# arduino-shield.net
KiCad netlist of a schematic drawn in EAGLE
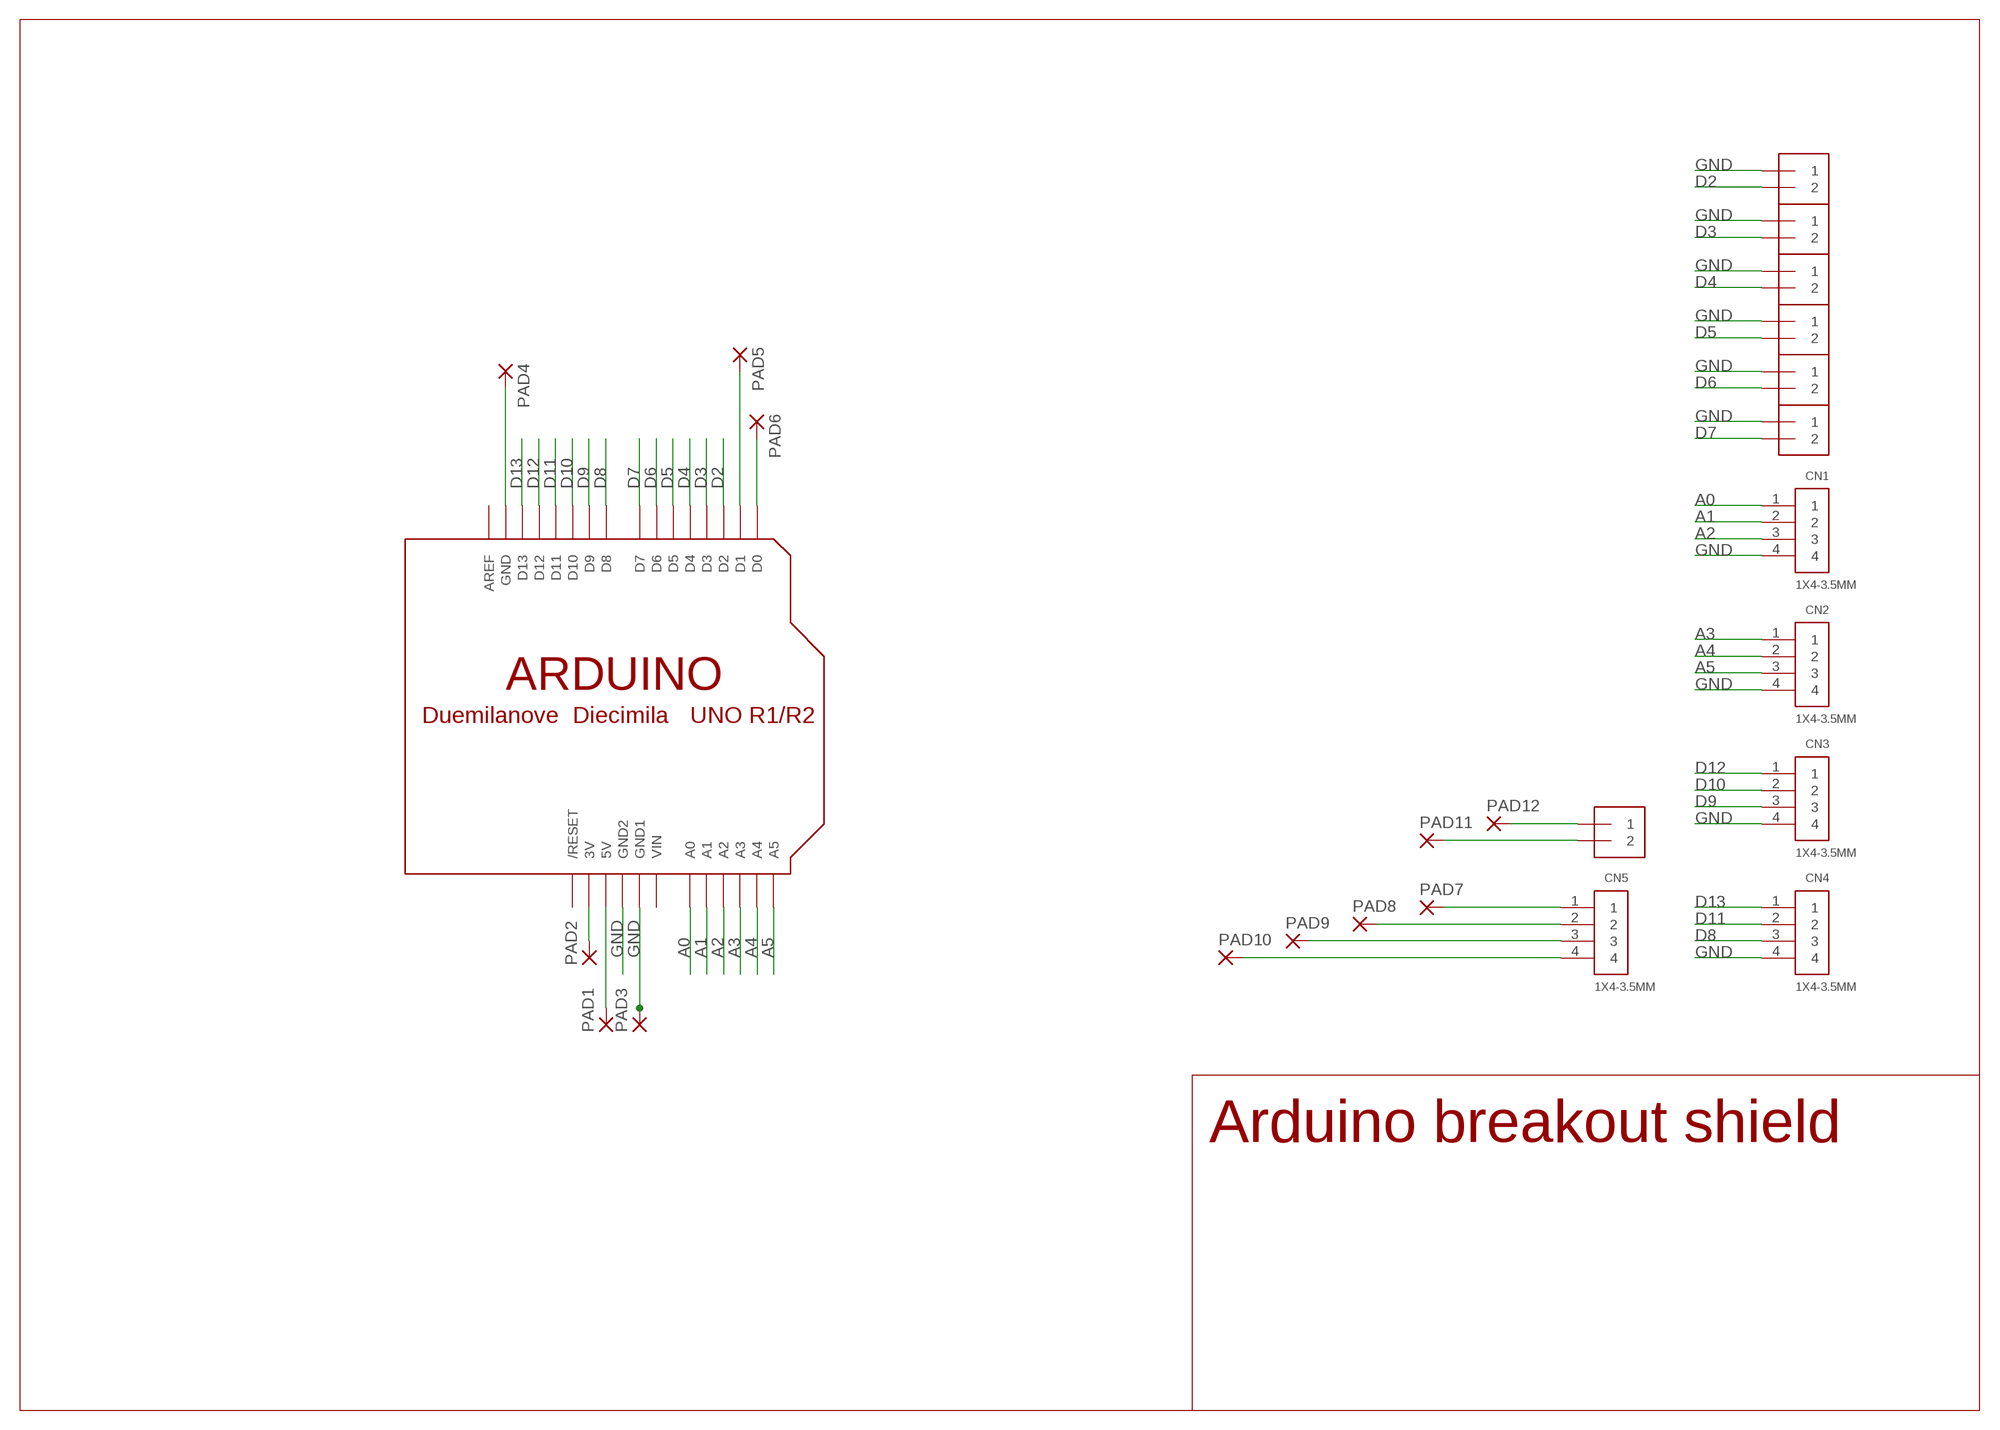
[diagram p0: schematic, sheet 1]
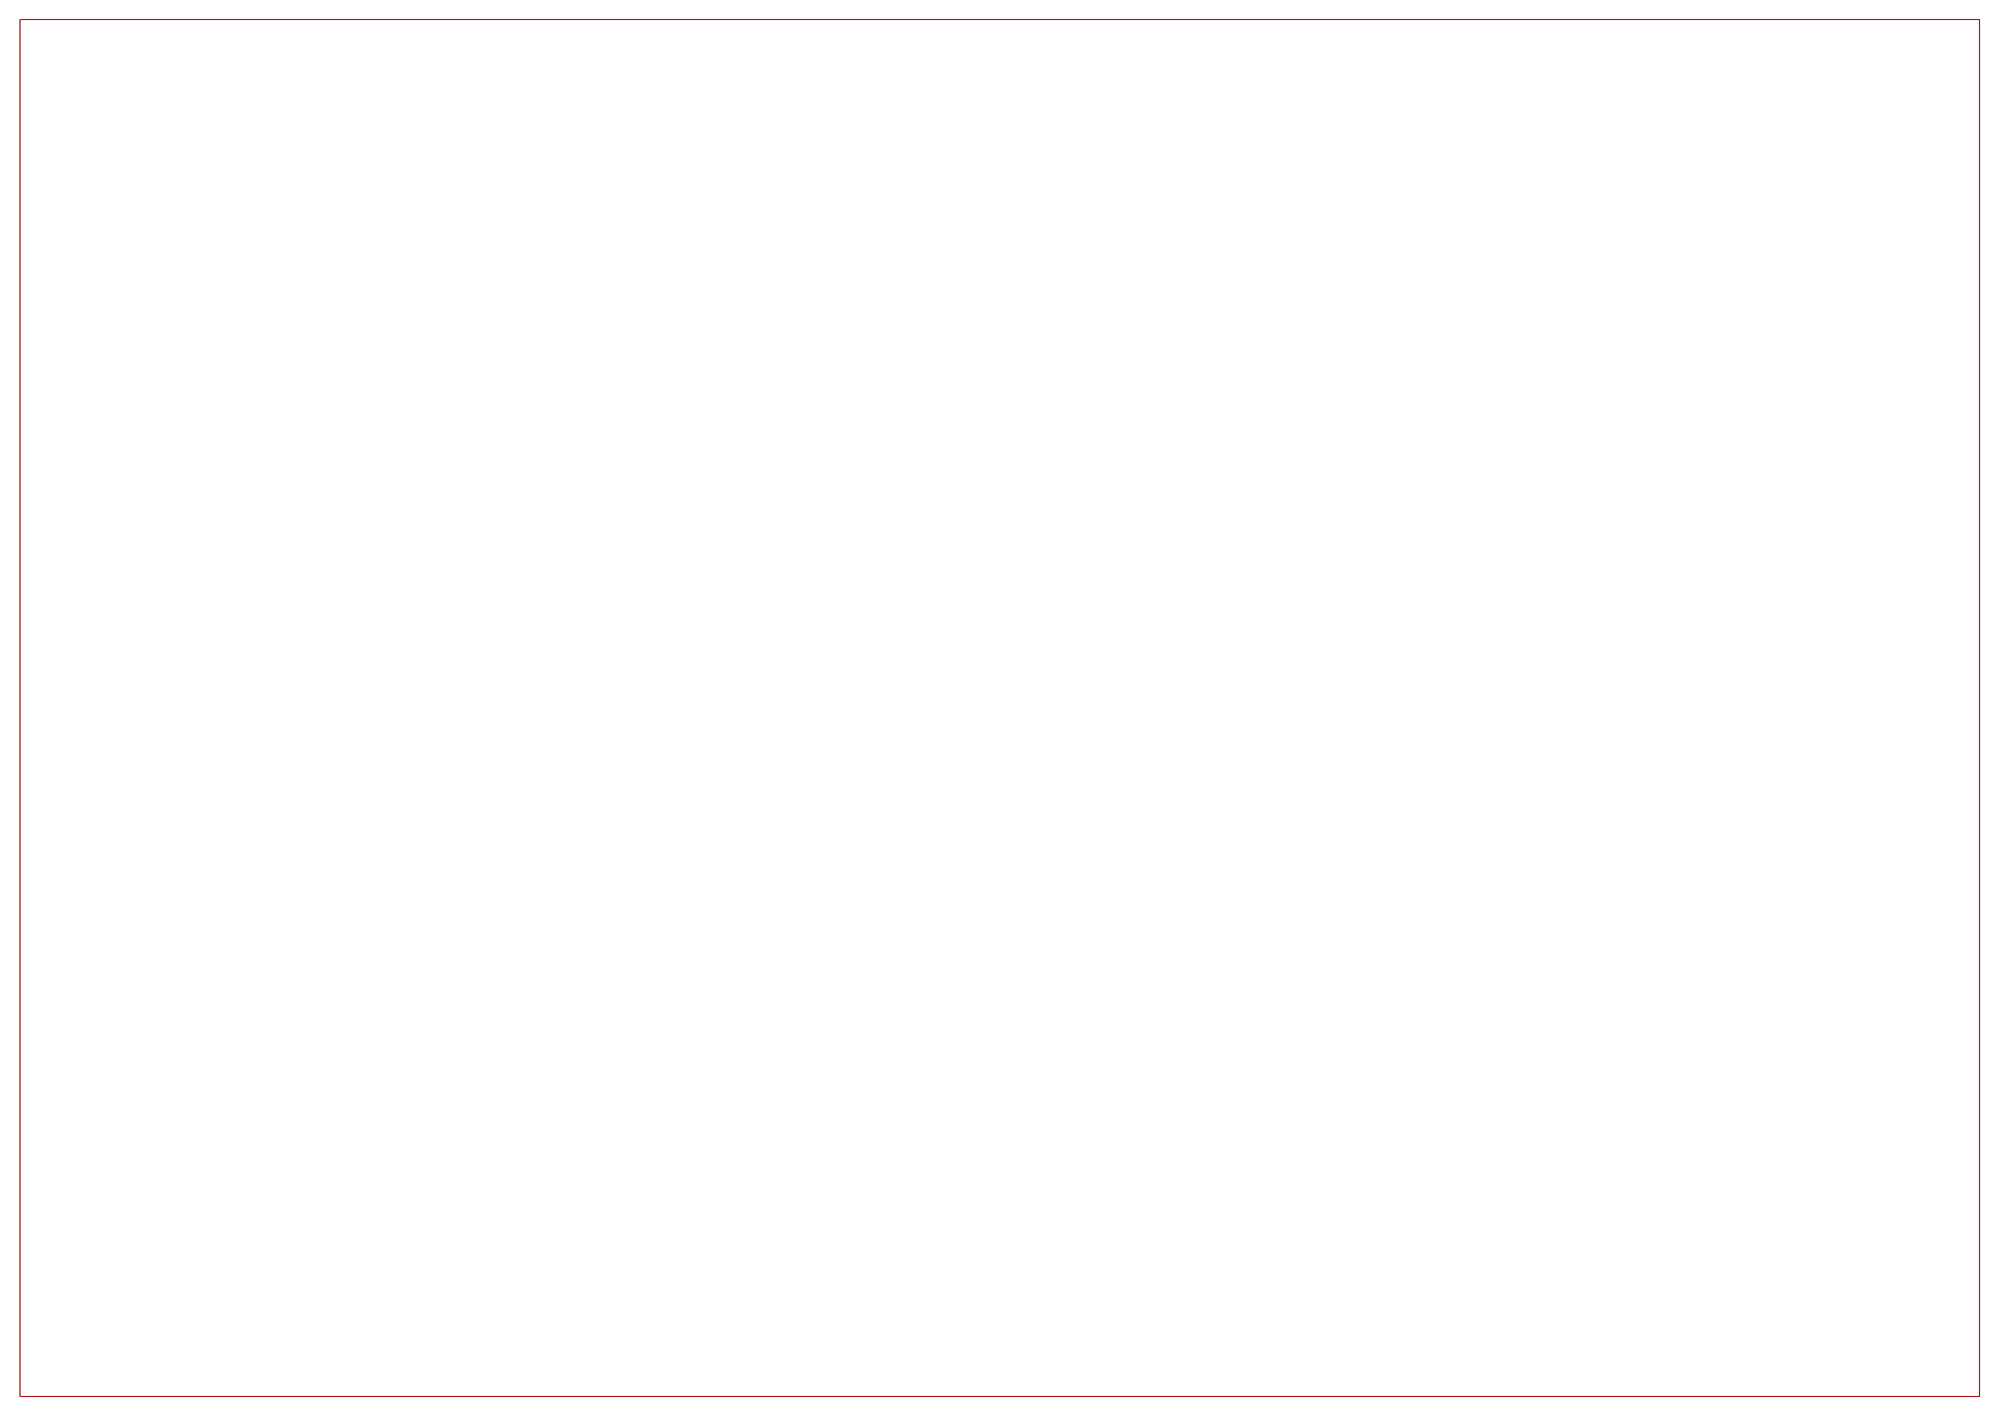
[diagram p1: schematic, sheet 2]

(export (version "E")
  (design (tool "Eeschema 10.0.6"))
  (components
    (comp (ref "CN1")
      (value "1X4-3.5MM")
      (footprint "eagle-import:1X04-3.5MM")
      (libsource (lib "eagle-import") (part "1X4-3.5MM"))
    )
    (comp (ref "CN2")
      (value "1X4-3.5MM")
      (footprint "eagle-import:1X04-3.5MM")
      (libsource (lib "eagle-import") (part "1X4-3.5MM"))
    )
    (comp (ref "CN3")
      (value "1X4-3.5MM")
      (footprint "eagle-import:1X04-3.5MM")
      (libsource (lib "eagle-import") (part "1X4-3.5MM"))
    )
    (comp (ref "CN4")
      (value "1X4-3.5MM")
      (footprint "eagle-import:1X04-3.5MM")
      (libsource (lib "eagle-import") (part "1X4-3.5MM"))
    )
    (comp (ref "CN5")
      (value "1X4-3.5MM")
      (footprint "eagle-import:1X04-3.5MM")
      (libsource (lib "eagle-import") (part "1X4-3.5MM"))
    )
    (comp (ref "J1")
      (value "1X2-3.5MM")
      (footprint "eagle-import:1X2-3.5MM")
      (libsource (lib "eagle-import") (part "1X2-3.5MM"))
    )
    (comp (ref "J2")
      (value "1X2-3.5MM")
      (footprint "eagle-import:1X2-3.5MM")
      (libsource (lib "eagle-import") (part "1X2-3.5MM"))
    )
    (comp (ref "J3")
      (value "1X2-3.5MM")
      (footprint "eagle-import:1X2-3.5MM")
      (libsource (lib "eagle-import") (part "1X2-3.5MM"))
    )
    (comp (ref "J4")
      (value "1X2-3.5MM")
      (footprint "eagle-import:1X2-3.5MM")
      (libsource (lib "eagle-import") (part "1X2-3.5MM"))
    )
    (comp (ref "J5")
      (value "1X2-3.5MM")
      (footprint "eagle-import:1X2-3.5MM")
      (libsource (lib "eagle-import") (part "1X2-3.5MM"))
    )
    (comp (ref "J6")
      (value "1X2-3.5MM")
      (footprint "eagle-import:1X2-3.5MM")
      (libsource (lib "eagle-import") (part "1X2-3.5MM"))
    )
    (comp (ref "J7")
      (value "1X2-3.5MM")
      (footprint "eagle-import:1X2-3.5MM")
      (libsource (lib "eagle-import") (part "1X2-3.5MM"))
    )
    (comp (ref "PAD1")
      (value "1,6/0,8")
      (footprint "eagle-import:1,6_0,8")
      (libsource (lib "eagle-import") (part "1,6/0,8"))
    )
    (comp (ref "PAD2")
      (value "1,6/0,8")
      (footprint "eagle-import:1,6_0,8")
      (libsource (lib "eagle-import") (part "1,6/0,8"))
    )
    (comp (ref "PAD3")
      (value "1,6/0,8")
      (footprint "eagle-import:1,6_0,8")
      (libsource (lib "eagle-import") (part "1,6/0,8"))
    )
    (comp (ref "PAD4")
      (value "1,6/0,8")
      (footprint "eagle-import:1,6_0,8")
      (libsource (lib "eagle-import") (part "1,6/0,8"))
    )
    (comp (ref "PAD5")
      (value "1,6/0,8")
      (footprint "eagle-import:1,6_0,8")
      (libsource (lib "eagle-import") (part "1,6/0,8"))
    )
    (comp (ref "PAD6")
      (value "1,6/0,8")
      (footprint "eagle-import:1,6_0,8")
      (libsource (lib "eagle-import") (part "1,6/0,8"))
    )
    (comp (ref "PAD7")
      (value "1,6/0,8")
      (footprint "eagle-import:1,6_0,8")
      (libsource (lib "eagle-import") (part "1,6/0,8"))
    )
    (comp (ref "PAD8")
      (value "1,6/0,8")
      (footprint "eagle-import:1,6_0,8")
      (libsource (lib "eagle-import") (part "1,6/0,8"))
    )
    (comp (ref "PAD9")
      (value "1,6/0,8")
      (footprint "eagle-import:1,6_0,8")
      (libsource (lib "eagle-import") (part "1,6/0,8"))
    )
    (comp (ref "PAD10")
      (value "1,6/0,8")
      (footprint "eagle-import:1,6_0,8")
      (libsource (lib "eagle-import") (part "1,6/0,8"))
    )
    (comp (ref "PAD11")
      (value "1,6/0,8")
      (footprint "eagle-import:1,6_0,8")
      (libsource (lib "eagle-import") (part "1,6/0,8"))
    )
    (comp (ref "PAD12")
      (value "1,6/0,8")
      (footprint "eagle-import:1,6_0,8")
      (libsource (lib "eagle-import") (part "1,6/0,8"))
    )
    (comp (ref "U$1")
      (value "ARDUINO-NOHOLE")
      (footprint "eagle-import:ARDUINO-NOHOLE")
      (libsource (lib "eagle-import") (part "ARDUINO-NOHOLE"))
    )
  )
  (nets
    (net (code "1") (name "A0") (class "Default")
      (node (ref "CN1") (pin "1") (pinfunction "1_1") (pintype "bidirectional"))
      (node (ref "U$1") (pin "A0") (pinfunction "A0_A0") (pintype "bidirectional"))
    )
    (net (code "2") (name "A1") (class "Default")
      (node (ref "CN1") (pin "2") (pinfunction "2_2") (pintype "bidirectional"))
      (node (ref "U$1") (pin "A1") (pinfunction "A1_A1") (pintype "bidirectional"))
    )
    (net (code "3") (name "A2") (class "Default")
      (node (ref "CN1") (pin "3") (pinfunction "3_3") (pintype "bidirectional"))
      (node (ref "U$1") (pin "A2") (pinfunction "A2_A2") (pintype "bidirectional"))
    )
    (net (code "4") (name "A3") (class "Default")
      (node (ref "CN2") (pin "1") (pinfunction "1_1") (pintype "bidirectional"))
      (node (ref "U$1") (pin "A3") (pinfunction "A3_A3") (pintype "bidirectional"))
    )
    (net (code "5") (name "A4") (class "Default")
      (node (ref "CN2") (pin "2") (pinfunction "2_2") (pintype "bidirectional"))
      (node (ref "U$1") (pin "A4") (pinfunction "A4_A4") (pintype "bidirectional"))
    )
    (net (code "6") (name "A5") (class "Default")
      (node (ref "CN2") (pin "3") (pinfunction "3_3") (pintype "bidirectional"))
      (node (ref "U$1") (pin "A5") (pinfunction "A5_A5") (pintype "bidirectional"))
    )
    (net (code "7") (name "D2") (class "Default")
      (node (ref "J1") (pin "2") (pinfunction "2_2") (pintype "passive"))
      (node (ref "U$1") (pin "D2") (pinfunction "D2_D2") (pintype "bidirectional"))
    )
    (net (code "8") (name "D3") (class "Default")
      (node (ref "J2") (pin "2") (pinfunction "2_2") (pintype "passive"))
      (node (ref "U$1") (pin "D3") (pinfunction "D3_D3") (pintype "bidirectional"))
    )
    (net (code "9") (name "D4") (class "Default")
      (node (ref "J3") (pin "2") (pinfunction "2_2") (pintype "passive"))
      (node (ref "U$1") (pin "D4") (pinfunction "D4_D4") (pintype "bidirectional"))
    )
    (net (code "10") (name "D5") (class "Default")
      (node (ref "J4") (pin "2") (pinfunction "2_2") (pintype "passive"))
      (node (ref "U$1") (pin "D5") (pinfunction "D5_D5") (pintype "bidirectional"))
    )
    (net (code "11") (name "D6") (class "Default")
      (node (ref "J5") (pin "2") (pinfunction "2_2") (pintype "passive"))
      (node (ref "U$1") (pin "D6") (pinfunction "D6_D6") (pintype "bidirectional"))
    )
    (net (code "12") (name "D7") (class "Default")
      (node (ref "J6") (pin "2") (pinfunction "2_2") (pintype "passive"))
      (node (ref "U$1") (pin "D7") (pinfunction "D7_D7") (pintype "bidirectional"))
    )
    (net (code "13") (name "D8") (class "Default")
      (node (ref "CN4") (pin "3") (pinfunction "3_3") (pintype "bidirectional"))
      (node (ref "U$1") (pin "D8") (pinfunction "D8_D8") (pintype "bidirectional"))
    )
    (net (code "14") (name "D9") (class "Default")
      (node (ref "CN3") (pin "3") (pinfunction "3_3") (pintype "bidirectional"))
      (node (ref "U$1") (pin "D9") (pinfunction "D9_D9") (pintype "bidirectional"))
    )
    (net (code "15") (name "D10") (class "Default")
      (node (ref "CN3") (pin "2") (pinfunction "2_2") (pintype "bidirectional"))
      (node (ref "U$1") (pin "D10") (pinfunction "D10_D10") (pintype "bidirectional"))
    )
    (net (code "16") (name "D11") (class "Default")
      (node (ref "CN4") (pin "2") (pinfunction "2_2") (pintype "bidirectional"))
      (node (ref "U$1") (pin "D11") (pinfunction "D11_D11") (pintype "bidirectional"))
    )
    (net (code "17") (name "D12") (class "Default")
      (node (ref "CN3") (pin "1") (pinfunction "1_1") (pintype "bidirectional"))
      (node (ref "U$1") (pin "D12") (pinfunction "D12_D12") (pintype "bidirectional"))
    )
    (net (code "18") (name "D13") (class "Default")
      (node (ref "CN4") (pin "1") (pinfunction "1_1") (pintype "bidirectional"))
      (node (ref "U$1") (pin "D13") (pinfunction "D13_D13") (pintype "bidirectional"))
    )
    (net (code "19") (name "GND") (class "Default")
      (node (ref "CN1") (pin "4") (pinfunction "4_4") (pintype "bidirectional"))
      (node (ref "CN2") (pin "4") (pinfunction "4_4") (pintype "bidirectional"))
      (node (ref "CN3") (pin "4") (pinfunction "4_4") (pintype "bidirectional"))
      (node (ref "CN4") (pin "4") (pinfunction "4_4") (pintype "bidirectional"))
      (node (ref "J1") (pin "1") (pinfunction "1_1") (pintype "passive"))
      (node (ref "J2") (pin "1") (pinfunction "1_1") (pintype "passive"))
      (node (ref "J3") (pin "1") (pinfunction "1_1") (pintype "passive"))
      (node (ref "J4") (pin "1") (pinfunction "1_1") (pintype "passive"))
      (node (ref "J5") (pin "1") (pinfunction "1_1") (pintype "passive"))
      (node (ref "J6") (pin "1") (pinfunction "1_1") (pintype "passive"))
      (node (ref "PAD3") (pin "1") (pinfunction "P_1") (pintype "passive"))
      (node (ref "U$1") (pin "GND1") (pinfunction "GND1_GND1") (pintype "power_in"))
      (node (ref "U$1") (pin "GND2") (pinfunction "GND2_GND2") (pintype "power_in"))
    )
    (net (code "20") (name "Net-(PAD1-P)") (class "Default")
      (node (ref "PAD1") (pin "1") (pinfunction "P_1") (pintype "passive"))
      (node (ref "U$1") (pin "5V") (pinfunction "5V_5V") (pintype "power_in"))
    )
    (net (code "21") (name "Net-(PAD2-P)") (class "Default")
      (node (ref "PAD2") (pin "1") (pinfunction "P_1") (pintype "passive"))
      (node (ref "U$1") (pin "3V") (pinfunction "3V_3V") (pintype "power_in"))
    )
    (net (code "22") (name "Net-(PAD4-P)") (class "Default")
      (node (ref "PAD4") (pin "1") (pinfunction "P_1") (pintype "passive"))
      (node (ref "U$1") (pin "GND") (pinfunction "GND_GND") (pintype "power_in"))
    )
    (net (code "23") (name "Net-(PAD5-P)") (class "Default")
      (node (ref "PAD5") (pin "1") (pinfunction "P_1") (pintype "passive"))
      (node (ref "U$1") (pin "D1") (pinfunction "D1_D1") (pintype "bidirectional"))
    )
    (net (code "24") (name "Net-(PAD6-P)") (class "Default")
      (node (ref "PAD6") (pin "1") (pinfunction "P_1") (pintype "passive"))
      (node (ref "U$1") (pin "D0") (pinfunction "D0_D0") (pintype "bidirectional"))
    )
    (net (code "25") (name "Net-(PAD7-P)") (class "Default")
      (node (ref "CN5") (pin "1") (pinfunction "1_1") (pintype "bidirectional"))
      (node (ref "PAD7") (pin "1") (pinfunction "P_1") (pintype "passive"))
    )
    (net (code "26") (name "Net-(PAD8-P)") (class "Default")
      (node (ref "CN5") (pin "2") (pinfunction "2_2") (pintype "bidirectional"))
      (node (ref "PAD8") (pin "1") (pinfunction "P_1") (pintype "passive"))
    )
    (net (code "27") (name "Net-(PAD9-P)") (class "Default")
      (node (ref "CN5") (pin "3") (pinfunction "3_3") (pintype "bidirectional"))
      (node (ref "PAD9") (pin "1") (pinfunction "P_1") (pintype "passive"))
    )
    (net (code "28") (name "Net-(PAD10-P)") (class "Default")
      (node (ref "CN5") (pin "4") (pinfunction "4_4") (pintype "bidirectional"))
      (node (ref "PAD10") (pin "1") (pinfunction "P_1") (pintype "passive"))
    )
    (net (code "29") (name "Net-(PAD11-P)") (class "Default")
      (node (ref "J7") (pin "2") (pinfunction "2_2") (pintype "passive"))
      (node (ref "PAD11") (pin "1") (pinfunction "P_1") (pintype "passive"))
    )
    (net (code "30") (name "Net-(PAD12-P)") (class "Default")
      (node (ref "J7") (pin "1") (pinfunction "1_1") (pintype "passive"))
      (node (ref "PAD12") (pin "1") (pinfunction "P_1") (pintype "passive"))
    )
    (net (code "31") (name "VIN") (class "Default")
      (node (ref "U$1") (pin "VIN") (pinfunction "VIN_VIN") (pintype "power_in"))
    )
    (net (code "32") (name "unconnected-(U$1-PadAREF)") (class "Default")
      (node (ref "U$1") (pin "AREF") (pinfunction "AREF_AREF") (pintype "bidirectional"))
    )
    (net (code "33") (name "unconnected-(U$1-{slash}RESET-PadRESET)") (class "Default")
      (node (ref "U$1") (pin "RESET") (pinfunction "/RESET_RESET") (pintype "bidirectional"))
    )
  )
)
